# Weatstone_bridge_part_I.net
KiCad netlist of a schematic drawn in Altium Designer
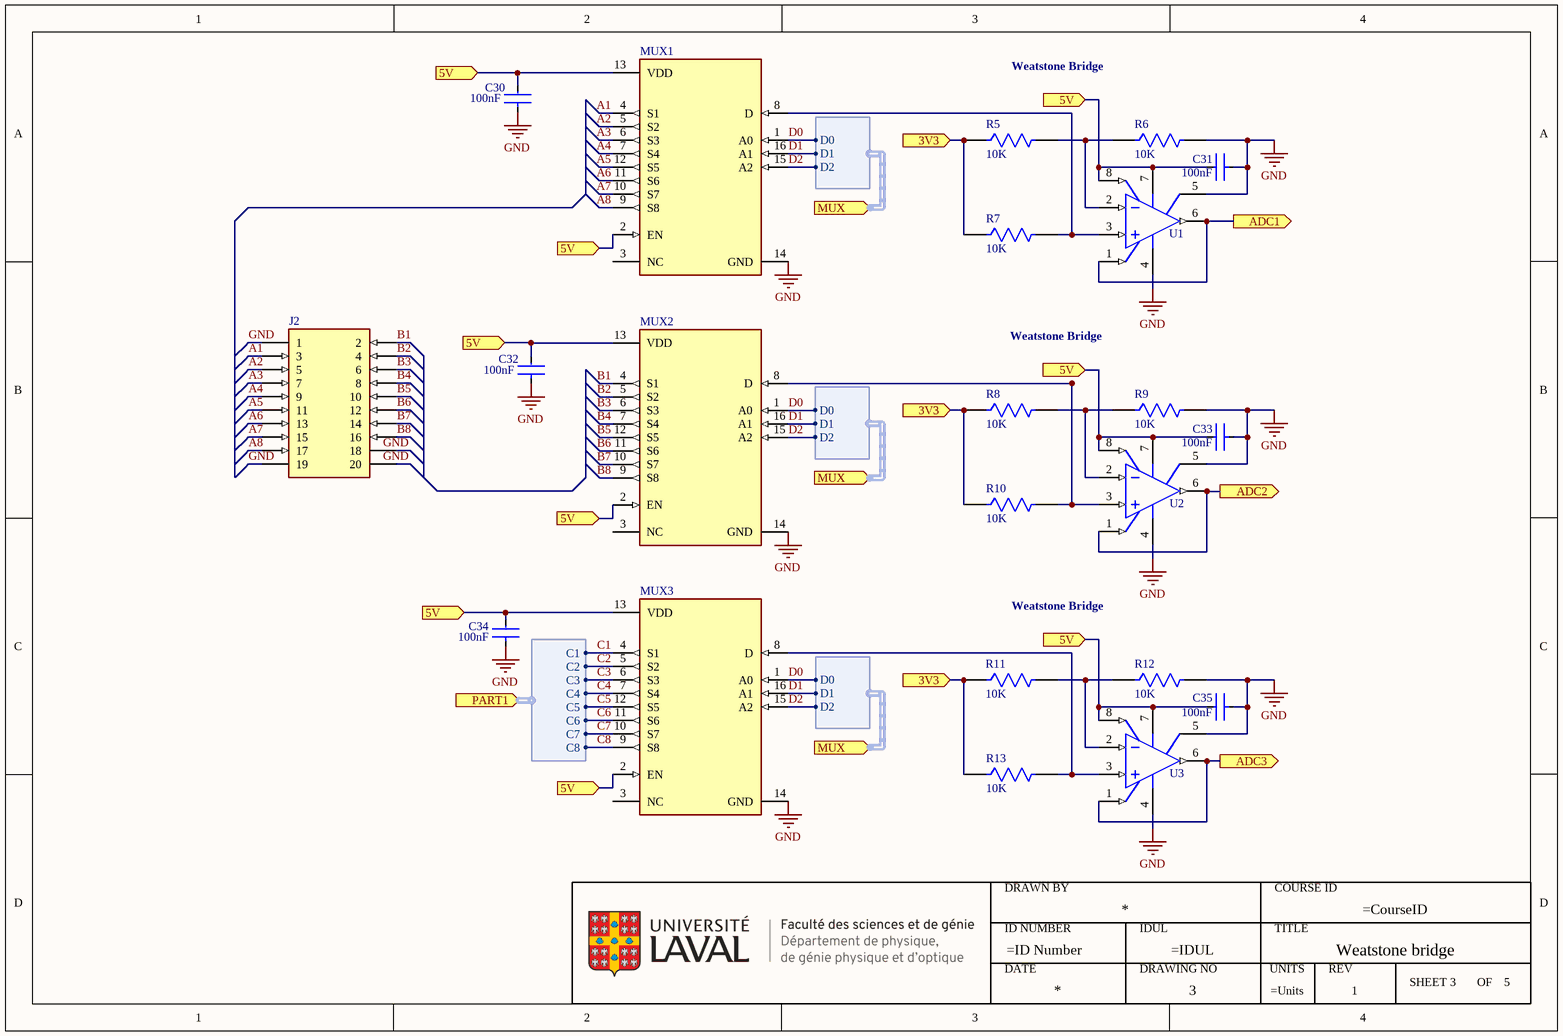
[diagram p0: Weatstone bridge part I.SchDoc]

(export (version "E")
  (design (tool "Eeschema 10.0.6"))
  (components
    (comp (ref "*3")
      (value "ULaval FSG-DPGPO")
      (libsource (lib "ULaval Title Block") (part "ULaval FSG-DPGPO"))
    )
    (comp (ref "C30")
      (value "100nF")
      (footprint "FP-CC0603-DA-IPC_B")
      (description "0603 0.1 uF 50 V ±5 % Tolerance X7R SMT Multilayer Ceramic Capacitor")
      (fields (field (name "TOLERANCE") "5%") (field (name "Comment") "CC0603JRX7R9BB104"))
      (libsource (lib "Laval University") (part "02cd4be3c70576c341d710602a673aa"))
    )
    (comp (ref "C31")
      (value "100nF")
      (footprint "FP-CC0603-DA-IPC_B")
      (description "0603 0.1 uF 50 V ±5 % Tolerance X7R SMT Multilayer Ceramic Capacitor")
      (fields (field (name "TOLERANCE") "5%") (field (name "Comment") "CC0603JRX7R9BB104"))
      (libsource (lib "Laval University") (part "02cd4be3c70576c341d710602a673aa"))
    )
    (comp (ref "C32")
      (value "100nF")
      (footprint "FP-CC0603-DA-IPC_B")
      (description "0603 0.1 uF 50 V ±5 % Tolerance X7R SMT Multilayer Ceramic Capacitor")
      (fields (field (name "TOLERANCE") "5%") (field (name "Comment") "CC0603JRX7R9BB104"))
      (libsource (lib "Laval University") (part "02cd4be3c70576c341d710602a673aa"))
    )
    (comp (ref "C33")
      (value "100nF")
      (footprint "FP-CC0603-DA-IPC_B")
      (description "0603 0.1 uF 50 V ±5 % Tolerance X7R SMT Multilayer Ceramic Capacitor")
      (fields (field (name "TOLERANCE") "5%") (field (name "Comment") "CC0603JRX7R9BB104"))
      (libsource (lib "Laval University") (part "02cd4be3c70576c341d710602a673aa"))
    )
    (comp (ref "C34")
      (value "100nF")
      (footprint "FP-CC0603-DA-IPC_B")
      (description "0603 0.1 uF 50 V ±5 % Tolerance X7R SMT Multilayer Ceramic Capacitor")
      (fields (field (name "TOLERANCE") "5%") (field (name "Comment") "CC0603JRX7R9BB104"))
      (libsource (lib "Laval University") (part "02cd4be3c70576c341d710602a673aa"))
    )
    (comp (ref "C35")
      (value "100nF")
      (footprint "FP-CC0603-DA-IPC_B")
      (description "0603 0.1 uF 50 V ±5 % Tolerance X7R SMT Multilayer Ceramic Capacitor")
      (fields (field (name "TOLERANCE") "5%") (field (name "Comment") "CC0603JRX7R9BB104"))
      (libsource (lib "Laval University") (part "02cd4be3c70576c341d710602a673aa"))
    )
    (comp (ref "J2")
      (value "SFC-110-T1-F-D-A")
      (footprint "SFC-110-T1-F-D-A-Footprint-2")
      (description "Headers & Wire Housings .050 Tiger Eye Cost-Effective Reliable Socket Strip")
      (libsource (lib "Laval University") (part "SFC-110-T1-F-D-A"))
    )
    (comp (ref "MUX1")
      (value "TMUX1208PWR")
      (footprint "FP-PW0016A-IPC_B")
      (description "5-V, 8: 1, 1-channel general-purpose analog multiplexer with 1.8-V input logic 16-TSSOP -40 to 125")
      (libsource (lib "Laval University") (part "3fc1eebd4caa5623a46538ca285a60d"))
    )
    (comp (ref "MUX2")
      (value "TMUX1208PWR")
      (footprint "FP-PW0016A-IPC_B")
      (description "5-V, 8: 1, 1-channel general-purpose analog multiplexer with 1.8-V input logic 16-TSSOP -40 to 125")
      (libsource (lib "Laval University") (part "3fc1eebd4caa5623a46538ca285a60d"))
    )
    (comp (ref "MUX3")
      (value "TMUX1208PWR")
      (footprint "FP-PW0016A-IPC_B")
      (description "5-V, 8: 1, 1-channel general-purpose analog multiplexer with 1.8-V input logic 16-TSSOP -40 to 125")
      (libsource (lib "Laval University") (part "3fc1eebd4caa5623a46538ca285a60d"))
    )
    (comp (ref "R5")
      (value "10K")
      (footprint "FP-RT0603-IPC_B")
      (description "Res High precision Thin Film 0603 10K Ohm 0.1% 1/10W ±25ppm/°C Molded SMD Paper T/R")
      (fields (field (name "Comment") "RT0603BRD0710KL"))
      (libsource (lib "Laval University") (part "1029c3af85768c4190bb7ad29bc67b5"))
    )
    (comp (ref "R6")
      (value "10K")
      (footprint "FP-RT0603-IPC_B")
      (description "Res High precision Thin Film 0603 10K Ohm 0.1% 1/10W ±25ppm/°C Molded SMD Paper T/R")
      (fields (field (name "Comment") "RT0603BRD0710KL"))
      (libsource (lib "Laval University") (part "1029c3af85768c4190bb7ad29bc67b5"))
    )
    (comp (ref "R7")
      (value "10K")
      (footprint "FP-RT0603-IPC_B")
      (description "Res High precision Thin Film 0603 10K Ohm 0.1% 1/10W ±25ppm/°C Molded SMD Paper T/R")
      (fields (field (name "Comment") "RT0603BRD0710KL"))
      (libsource (lib "Laval University") (part "1029c3af85768c4190bb7ad29bc67b5"))
    )
    (comp (ref "R8")
      (value "10K")
      (footprint "FP-RT0603-IPC_B")
      (description "Res High precision Thin Film 0603 10K Ohm 0.1% 1/10W ±25ppm/°C Molded SMD Paper T/R")
      (fields (field (name "Comment") "RT0603BRD0710KL"))
      (libsource (lib "Laval University") (part "1029c3af85768c4190bb7ad29bc67b5"))
    )
    (comp (ref "R9")
      (value "10K")
      (footprint "FP-RT0603-IPC_B")
      (description "Res High precision Thin Film 0603 10K Ohm 0.1% 1/10W ±25ppm/°C Molded SMD Paper T/R")
      (fields (field (name "Comment") "RT0603BRD0710KL"))
      (libsource (lib "Laval University") (part "1029c3af85768c4190bb7ad29bc67b5"))
    )
    (comp (ref "R10")
      (value "10K")
      (footprint "FP-RT0603-IPC_B")
      (description "Res High precision Thin Film 0603 10K Ohm 0.1% 1/10W ±25ppm/°C Molded SMD Paper T/R")
      (fields (field (name "Comment") "RT0603BRD0710KL"))
      (libsource (lib "Laval University") (part "1029c3af85768c4190bb7ad29bc67b5"))
    )
    (comp (ref "R11")
      (value "10K")
      (footprint "FP-RT0603-IPC_B")
      (description "Res High precision Thin Film 0603 10K Ohm 0.1% 1/10W ±25ppm/°C Molded SMD Paper T/R")
      (fields (field (name "Comment") "RT0603BRD0710KL"))
      (libsource (lib "Laval University") (part "1029c3af85768c4190bb7ad29bc67b5"))
    )
    (comp (ref "R12")
      (value "10K")
      (footprint "FP-RT0603-IPC_B")
      (description "Res High precision Thin Film 0603 10K Ohm 0.1% 1/10W ±25ppm/°C Molded SMD Paper T/R")
      (fields (field (name "Comment") "RT0603BRD0710KL"))
      (libsource (lib "Laval University") (part "1029c3af85768c4190bb7ad29bc67b5"))
    )
    (comp (ref "R13")
      (value "10K")
      (footprint "FP-RT0603-IPC_B")
      (description "Res High precision Thin Film 0603 10K Ohm 0.1% 1/10W ±25ppm/°C Molded SMD Paper T/R")
      (fields (field (name "Comment") "RT0603BRD0710KL"))
      (libsource (lib "Laval University") (part "1029c3af85768c4190bb7ad29bc67b5"))
    )
    (comp (ref "U1")
      (value "MCP6N11-100E/SN")
      (footprint "MCP6N11-100E/SN")
      (description "MCP6N11 Series Single Channel 500 KHz 5.5 V Instrumentation Amplifier - SOIC-8")
      (libsource (lib "Laval University") (part "AMP-INA-MCP6N11-IL8"))
    )
    (comp (ref "U2")
      (value "MCP6N11-100E/SN")
      (footprint "MCP6N11-100E/SN")
      (description "MCP6N11 Series Single Channel 500 KHz 5.5 V Instrumentation Amplifier - SOIC-8")
      (libsource (lib "Laval University") (part "AMP-INA-MCP6N11-IL8"))
    )
    (comp (ref "U3")
      (value "MCP6N11-100E/SN")
      (footprint "MCP6N11-100E/SN")
      (description "MCP6N11 Series Single Channel 500 KHz 5.5 V Instrumentation Amplifier - SOIC-8")
      (libsource (lib "Laval University") (part "AMP-INA-MCP6N11-IL8"))
    )
  )
  (nets
    (net (code "3") (name "/3V3") (class "Default")
      (node (ref "R10") (pin "1") (pinfunction "1_1") (pintype "passive"))
      (node (ref "R11") (pin "1") (pinfunction "1_1") (pintype "passive"))
      (node (ref "R13") (pin "1") (pinfunction "1_1") (pintype "passive"))
      (node (ref "R5") (pin "1") (pinfunction "1_1") (pintype "passive"))
      (node (ref "R7") (pin "1") (pinfunction "1_1") (pintype "passive"))
      (node (ref "R8") (pin "1") (pinfunction "1_1") (pintype "passive"))
    )
    (net (code "4") (name "/5V") (class "Default")
      (node (ref "C30") (pin "2") (pinfunction "2_2") (pintype "passive"))
      (node (ref "C31") (pin "2") (pinfunction "2_2") (pintype "passive"))
      (node (ref "C32") (pin "2") (pinfunction "2_2") (pintype "passive"))
      (node (ref "C33") (pin "2") (pinfunction "2_2") (pintype "passive"))
      (node (ref "C34") (pin "2") (pinfunction "2_2") (pintype "passive"))
      (node (ref "C35") (pin "2") (pinfunction "2_2") (pintype "passive"))
      (node (ref "MUX1") (pin "13") (pinfunction "VDD_13") (pintype "power_in"))
      (node (ref "MUX1") (pin "2") (pinfunction "EN_2") (pintype "input"))
      (node (ref "MUX2") (pin "13") (pinfunction "VDD_13") (pintype "power_in"))
      (node (ref "MUX2") (pin "2") (pinfunction "EN_2") (pintype "input"))
      (node (ref "MUX3") (pin "13") (pinfunction "VDD_13") (pintype "power_in"))
      (node (ref "MUX3") (pin "2") (pinfunction "EN_2") (pintype "input"))
      (node (ref "U1") (pin "7") (pinfunction "VDD_7") (pintype "power_in"))
      (node (ref "U1") (pin "8") (pinfunction "EN/~{CAL}_8") (pintype "input"))
      (node (ref "U2") (pin "7") (pinfunction "VDD_7") (pintype "power_in"))
      (node (ref "U2") (pin "8") (pinfunction "EN/~{CAL}_8") (pintype "input"))
      (node (ref "U3") (pin "7") (pinfunction "VDD_7") (pintype "power_in"))
      (node (ref "U3") (pin "8") (pinfunction "EN/~{CAL}_8") (pintype "input"))
    )
    (net (code "5") (name "/A1") (class "Default")
      (node (ref "J2") (pin "3") (pinfunction "3_3") (pintype "input"))
      (node (ref "MUX1") (pin "4") (pinfunction "S1_4") (pintype "output"))
    )
    (net (code "6") (name "/A2") (class "Default")
      (node (ref "J2") (pin "5") (pinfunction "5_5") (pintype "input"))
      (node (ref "MUX1") (pin "5") (pinfunction "S2_5") (pintype "output"))
    )
    (net (code "7") (name "/A3") (class "Default")
      (node (ref "J2") (pin "7") (pinfunction "7_7") (pintype "input"))
      (node (ref "MUX1") (pin "6") (pinfunction "S3_6") (pintype "output"))
    )
    (net (code "8") (name "/A4") (class "Default")
      (node (ref "J2") (pin "9") (pinfunction "9_9") (pintype "input"))
      (node (ref "MUX1") (pin "7") (pinfunction "S4_7") (pintype "output"))
    )
    (net (code "9") (name "/A5") (class "Default")
      (node (ref "J2") (pin "11") (pinfunction "11_11") (pintype "input"))
      (node (ref "MUX1") (pin "12") (pinfunction "S5_12") (pintype "output"))
    )
    (net (code "10") (name "/A6") (class "Default")
      (node (ref "J2") (pin "13") (pinfunction "13_13") (pintype "input"))
      (node (ref "MUX1") (pin "11") (pinfunction "S6_11") (pintype "output"))
    )
    (net (code "11") (name "/A7") (class "Default")
      (node (ref "J2") (pin "15") (pinfunction "15_15") (pintype "input"))
      (node (ref "MUX1") (pin "10") (pinfunction "S7_10") (pintype "output"))
    )
    (net (code "12") (name "/A8") (class "Default")
      (node (ref "J2") (pin "17") (pinfunction "17_17") (pintype "input"))
      (node (ref "MUX1") (pin "9") (pinfunction "S8_9") (pintype "output"))
    )
    (net (code "13") (name "/ADC1") (class "Default")
      (node (ref "U1") (pin "1") (pinfunction "VFG_1") (pintype "input"))
      (node (ref "U1") (pin "6") (pinfunction "VOUT_6") (pintype "output"))
    )
    (net (code "14") (name "/ADC2") (class "Default")
      (node (ref "U2") (pin "1") (pinfunction "VFG_1") (pintype "input"))
      (node (ref "U2") (pin "6") (pinfunction "VOUT_6") (pintype "output"))
    )
    (net (code "15") (name "/ADC3") (class "Default")
      (node (ref "U3") (pin "1") (pinfunction "VFG_1") (pintype "input"))
      (node (ref "U3") (pin "6") (pinfunction "VOUT_6") (pintype "output"))
    )
    (net (code "16") (name "/B1") (class "Default")
      (node (ref "J2") (pin "2") (pinfunction "2_2") (pintype "input"))
      (node (ref "MUX2") (pin "4") (pinfunction "S1_4") (pintype "output"))
    )
    (net (code "17") (name "/B2") (class "Default")
      (node (ref "J2") (pin "4") (pinfunction "4_4") (pintype "input"))
      (node (ref "MUX2") (pin "5") (pinfunction "S2_5") (pintype "output"))
    )
    (net (code "18") (name "/B3") (class "Default")
      (node (ref "J2") (pin "6") (pinfunction "6_6") (pintype "input"))
      (node (ref "MUX2") (pin "6") (pinfunction "S3_6") (pintype "output"))
    )
    (net (code "19") (name "/B4") (class "Default")
      (node (ref "J2") (pin "8") (pinfunction "8_8") (pintype "input"))
      (node (ref "MUX2") (pin "7") (pinfunction "S4_7") (pintype "output"))
    )
    (net (code "20") (name "/B5") (class "Default")
      (node (ref "J2") (pin "10") (pinfunction "10_10") (pintype "input"))
      (node (ref "MUX2") (pin "12") (pinfunction "S5_12") (pintype "output"))
    )
    (net (code "21") (name "/B6") (class "Default")
      (node (ref "J2") (pin "12") (pinfunction "12_12") (pintype "input"))
      (node (ref "MUX2") (pin "11") (pinfunction "S6_11") (pintype "output"))
    )
    (net (code "22") (name "/B7") (class "Default")
      (node (ref "J2") (pin "14") (pinfunction "14_14") (pintype "input"))
      (node (ref "MUX2") (pin "10") (pinfunction "S7_10") (pintype "output"))
    )
    (net (code "23") (name "/B8") (class "Default")
      (node (ref "J2") (pin "16") (pinfunction "16_16") (pintype "input"))
      (node (ref "MUX2") (pin "9") (pinfunction "S8_9") (pintype "output"))
    )
    (net (code "24") (name "/C1") (class "Default")
      (node (ref "MUX3") (pin "4") (pinfunction "S1_4") (pintype "output"))
    )
    (net (code "25") (name "/C2") (class "Default")
      (node (ref "MUX3") (pin "5") (pinfunction "S2_5") (pintype "output"))
    )
    (net (code "26") (name "/C3") (class "Default")
      (node (ref "MUX3") (pin "6") (pinfunction "S3_6") (pintype "output"))
    )
    (net (code "27") (name "/C4") (class "Default")
      (node (ref "MUX3") (pin "7") (pinfunction "S4_7") (pintype "output"))
    )
    (net (code "28") (name "/C5") (class "Default")
      (node (ref "MUX3") (pin "12") (pinfunction "S5_12") (pintype "output"))
    )
    (net (code "29") (name "/C6") (class "Default")
      (node (ref "MUX3") (pin "11") (pinfunction "S6_11") (pintype "output"))
    )
    (net (code "30") (name "/C7") (class "Default")
      (node (ref "MUX3") (pin "10") (pinfunction "S7_10") (pintype "output"))
    )
    (net (code "31") (name "/C8") (class "Default")
      (node (ref "MUX3") (pin "9") (pinfunction "S8_9") (pintype "output"))
    )
    (net (code "32") (name "/D0") (class "Default")
      (node (ref "MUX1") (pin "1") (pinfunction "A0_1") (pintype "input"))
      (node (ref "MUX2") (pin "1") (pinfunction "A0_1") (pintype "input"))
      (node (ref "MUX3") (pin "1") (pinfunction "A0_1") (pintype "input"))
    )
    (net (code "33") (name "/D1") (class "Default")
      (node (ref "MUX1") (pin "16") (pinfunction "A1_16") (pintype "input"))
      (node (ref "MUX2") (pin "16") (pinfunction "A1_16") (pintype "input"))
      (node (ref "MUX3") (pin "16") (pinfunction "A1_16") (pintype "input"))
    )
    (net (code "34") (name "/D2") (class "Default")
      (node (ref "MUX1") (pin "15") (pinfunction "A2_15") (pintype "input"))
      (node (ref "MUX2") (pin "15") (pinfunction "A2_15") (pintype "input"))
      (node (ref "MUX3") (pin "15") (pinfunction "A2_15") (pintype "input"))
    )
    (net (code "37") (name "GND") (class "Default")
      (node (ref "C30") (pin "1") (pinfunction "1_1") (pintype "passive"))
      (node (ref "C31") (pin "1") (pinfunction "1_1") (pintype "passive"))
      (node (ref "C32") (pin "1") (pinfunction "1_1") (pintype "passive"))
      (node (ref "C33") (pin "1") (pinfunction "1_1") (pintype "passive"))
      (node (ref "C34") (pin "1") (pinfunction "1_1") (pintype "passive"))
      (node (ref "C35") (pin "1") (pinfunction "1_1") (pintype "passive"))
      (node (ref "J2") (pin "1") (pinfunction "1_1") (pintype "power_in"))
      (node (ref "J2") (pin "18") (pinfunction "18_18") (pintype "power_in"))
      (node (ref "J2") (pin "19") (pinfunction "19_19") (pintype "power_in"))
      (node (ref "J2") (pin "20") (pinfunction "20_20") (pintype "power_in"))
      (node (ref "MUX1") (pin "14") (pinfunction "GND_14") (pintype "power_in"))
      (node (ref "MUX2") (pin "14") (pinfunction "GND_14") (pintype "power_in"))
      (node (ref "MUX3") (pin "14") (pinfunction "GND_14") (pintype "power_in"))
      (node (ref "R12") (pin "2") (pinfunction "2_2") (pintype "passive"))
      (node (ref "R6") (pin "2") (pinfunction "2_2") (pintype "passive"))
      (node (ref "R9") (pin "2") (pinfunction "2_2") (pintype "passive"))
      (node (ref "U1") (pin "4") (pinfunction "VSS_4") (pintype "power_in"))
      (node (ref "U1") (pin "5") (pinfunction "VREF_5") (pintype "power_in"))
      (node (ref "U2") (pin "4") (pinfunction "VSS_4") (pintype "power_in"))
      (node (ref "U2") (pin "5") (pinfunction "VREF_5") (pintype "power_in"))
      (node (ref "U3") (pin "4") (pinfunction "VSS_4") (pintype "power_in"))
      (node (ref "U3") (pin "5") (pinfunction "VREF_5") (pintype "power_in"))
    )
    (net (code "38") (name "Net-(MUX1-D)") (class "Default")
      (node (ref "MUX1") (pin "8") (pinfunction "D_8") (pintype "input"))
      (node (ref "R7") (pin "2") (pinfunction "2_2") (pintype "passive"))
      (node (ref "U1") (pin "3") (pinfunction "VIP_3") (pintype "input"))
    )
    (net (code "39") (name "Net-(MUX2-D)") (class "Default")
      (node (ref "MUX2") (pin "8") (pinfunction "D_8") (pintype "input"))
      (node (ref "R10") (pin "2") (pinfunction "2_2") (pintype "passive"))
      (node (ref "U2") (pin "3") (pinfunction "VIP_3") (pintype "input"))
    )
    (net (code "40") (name "Net-(MUX3-D)") (class "Default")
      (node (ref "MUX3") (pin "8") (pinfunction "D_8") (pintype "input"))
      (node (ref "R13") (pin "2") (pinfunction "2_2") (pintype "passive"))
      (node (ref "U3") (pin "3") (pinfunction "VIP_3") (pintype "input"))
    )
    (net (code "41") (name "Net-(U1-VIM)") (class "Default")
      (node (ref "R5") (pin "2") (pinfunction "2_2") (pintype "passive"))
      (node (ref "R6") (pin "1") (pinfunction "1_1") (pintype "passive"))
      (node (ref "U1") (pin "2") (pinfunction "VIM_2") (pintype "input"))
    )
    (net (code "42") (name "Net-(U2-VIM)") (class "Default")
      (node (ref "R8") (pin "2") (pinfunction "2_2") (pintype "passive"))
      (node (ref "R9") (pin "1") (pinfunction "1_1") (pintype "passive"))
      (node (ref "U2") (pin "2") (pinfunction "VIM_2") (pintype "input"))
    )
    (net (code "43") (name "Net-(U3-VIM)") (class "Default")
      (node (ref "R11") (pin "2") (pinfunction "2_2") (pintype "passive"))
      (node (ref "R12") (pin "1") (pinfunction "1_1") (pintype "passive"))
      (node (ref "U3") (pin "2") (pinfunction "VIM_2") (pintype "input"))
    )
    (net (code "44") (name "unconnected-(MUX1-NC-Pad3)") (class "Default")
      (node (ref "MUX1") (pin "3") (pinfunction "NC_3") (pintype "tri_state"))
    )
    (net (code "45") (name "unconnected-(MUX2-NC-Pad3)") (class "Default")
      (node (ref "MUX2") (pin "3") (pinfunction "NC_3") (pintype "tri_state"))
    )
    (net (code "46") (name "unconnected-(MUX3-NC-Pad3)") (class "Default")
      (node (ref "MUX3") (pin "3") (pinfunction "NC_3") (pintype "tri_state"))
    )
  )
)
